# CAN.net
KiCad netlist of a schematic drawn in Altium Designer
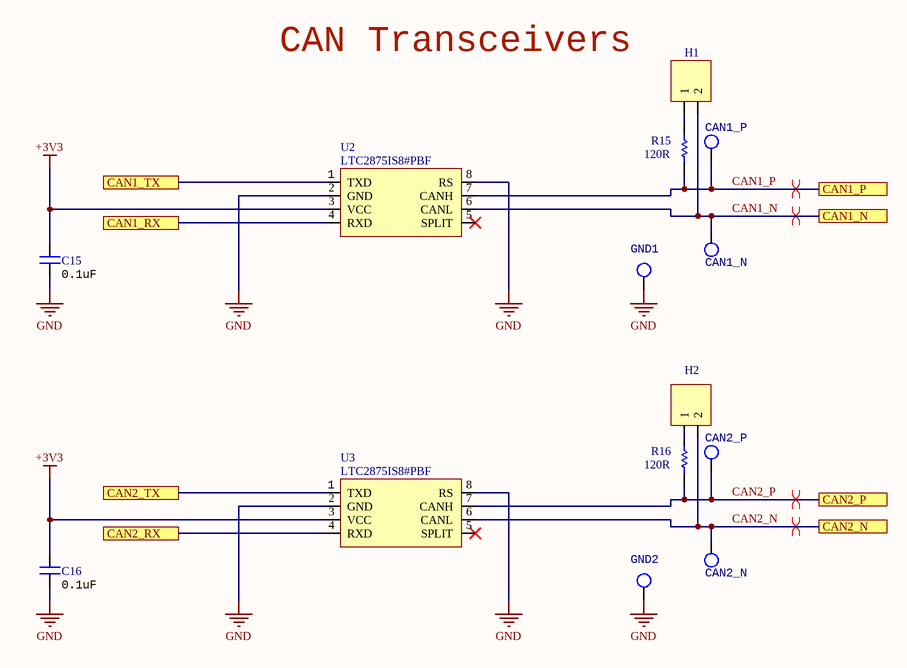
[diagram p0: CAN.SchDoc]

(export (version "E")
  (design (tool "Eeschema 10.0.6"))
  (components
    (comp (ref "C15")
      (value "0.1uF")
      (footprint "CAPC0603(1608)55_N")
      (description "CAP CER 0.1UF 16V X7R 0603")
      (fields (field (name "MPN") "CC0603KRX7R7BB104") (field (name "MANUFACTURER") "Yageo"))
      (libsource (lib "UWRT_Schematic_Library_2020") (part "CAP_0.1uF_16V_0603"))
    )
    (comp (ref "C16")
      (value "0.1uF")
      (footprint "CAPC0603(1608)55_N")
      (description "CAP CER 0.1UF 16V X7R 0603")
      (fields (field (name "MPN") "CC0603KRX7R7BB104") (field (name "MANUFACTURER") "Yageo"))
      (libsource (lib "UWRT_Schematic_Library_2020") (part "CAP_0.1uF_16V_0603"))
    )
    (comp (ref "CAN1_N")
      (value "TESTPOINT_LOOP")
      (footprint "TESTPOINT_LOOP")
      (description "Loop testpoint through-hole pad")
      (fields (field (name "MANUFACTURER") "Keystone Electronics"))
      (libsource (lib "UWRT_Schematic_Library_2020") (part "TESTPOINT_LOOP"))
    )
    (comp (ref "CAN1_P")
      (value "TESTPOINT_LOOP")
      (footprint "TESTPOINT_LOOP")
      (description "Loop testpoint through-hole pad")
      (fields (field (name "MANUFACTURER") "Keystone Electronics"))
      (libsource (lib "UWRT_Schematic_Library_2020") (part "TESTPOINT_LOOP"))
    )
    (comp (ref "CAN2_N")
      (value "TESTPOINT_LOOP")
      (footprint "TESTPOINT_LOOP")
      (description "Loop testpoint through-hole pad")
      (fields (field (name "MANUFACTURER") "Keystone Electronics"))
      (libsource (lib "UWRT_Schematic_Library_2020") (part "TESTPOINT_LOOP"))
    )
    (comp (ref "CAN2_P")
      (value "TESTPOINT_LOOP")
      (footprint "TESTPOINT_LOOP")
      (description "Loop testpoint through-hole pad")
      (fields (field (name "MANUFACTURER") "Keystone Electronics"))
      (libsource (lib "UWRT_Schematic_Library_2020") (part "TESTPOINT_LOOP"))
    )
    (comp (ref "GND1")
      (value "TESTPOINT_LOOP")
      (footprint "TESTPOINT_LOOP")
      (description "Loop testpoint through-hole pad")
      (fields (field (name "MANUFACTURER") "Keystone Electronics"))
      (libsource (lib "UWRT_Schematic_Library_2020") (part "TESTPOINT_LOOP"))
    )
    (comp (ref "GND2")
      (value "TESTPOINT_LOOP")
      (footprint "TESTPOINT_LOOP")
      (description "Loop testpoint through-hole pad")
      (fields (field (name "MANUFACTURER") "Keystone Electronics"))
      (libsource (lib "UWRT_Schematic_Library_2020") (part "TESTPOINT_LOOP"))
    )
    (comp (ref "H1")
      (value "JUMPER_2")
      (footprint "HDR1X2")
      (description "HEADER 2X1")
      (libsource (lib "UWRT_Schematic_Library_2020") (part "JUMPER_2"))
    )
    (comp (ref "H2")
      (value "JUMPER_2")
      (footprint "HDR1X2")
      (description "HEADER 2X1")
      (libsource (lib "UWRT_Schematic_Library_2020") (part "JUMPER_2"))
    )
    (comp (ref "R15")
      (value "120R")
      (footprint "RESC0603(1608)_N")
      (description "RES SMD 120 OHM 5% 1/10W 0603")
      (fields (field (name "MANUFACTURER") "Yageo") (field (name "MPN") "RC0603JR-07120RL"))
      (libsource (lib "UWRT_Schematic_Library_2020") (part "RES_120R_0603"))
    )
    (comp (ref "R16")
      (value "120R")
      (footprint "RESC0603(1608)_N")
      (description "RES SMD 120 OHM 5% 1/10W 0603")
      (fields (field (name "MANUFACTURER") "Yageo") (field (name "MPN") "RC0603JR-07120RL"))
      (libsource (lib "UWRT_Schematic_Library_2020") (part "RES_120R_0603"))
    )
    (comp (ref "U2")
      (value "IC TXRX CAN")
      (footprint "LT-S8_N")
      (description "IC TXRX CAN 4MBPS 8SO")
      (fields (field (name "MANUFACTURER") "Linear Technologies") (field (name "MPN") "LTC2875IS8#PBF"))
      (libsource (lib "UWRT_Schematic_Library_2020") (part "LTC2875"))
    )
    (comp (ref "U3")
      (value "IC TXRX CAN")
      (footprint "LT-S8_N")
      (description "IC TXRX CAN 4MBPS 8SO")
      (fields (field (name "MANUFACTURER") "Linear Technologies") (field (name "MPN") "LTC2875IS8#PBF"))
      (libsource (lib "UWRT_Schematic_Library_2020") (part "LTC2875"))
    )
  )
  (nets
    (net (code "1") (name "+3V3") (class "Default")
      (node (ref "C15") (pin "2") (pinfunction "2_2") (pintype "passive"))
      (node (ref "C16") (pin "2") (pinfunction "2_2") (pintype "passive"))
      (node (ref "U2") (pin "3") (pinfunction "VCC_3") (pintype "passive"))
      (node (ref "U3") (pin "3") (pinfunction "VCC_3") (pintype "passive"))
    )
    (net (code "2") (name "/CAN1_N") (class "Default")
      (node (ref "CAN1_N") (pin "1") (pintype "passive"))
      (node (ref "H1") (pin "2") (pinfunction "2_2") (pintype "passive"))
      (node (ref "U2") (pin "6") (pinfunction "CANL_6") (pintype "passive"))
    )
    (net (code "3") (name "/CAN1_P") (class "Default")
      (node (ref "CAN1_P") (pin "1") (pintype "passive"))
      (node (ref "R15") (pin "1") (pinfunction "1_1") (pintype "passive"))
      (node (ref "U2") (pin "7") (pinfunction "CANH_7") (pintype "passive"))
    )
    (net (code "4") (name "/CAN1_RX") (class "Default")
      (node (ref "U2") (pin "4") (pinfunction "RXD_4") (pintype "passive"))
    )
    (net (code "5") (name "/CAN1_TX") (class "Default")
      (node (ref "U2") (pin "1") (pinfunction "TXD_1") (pintype "passive"))
    )
    (net (code "6") (name "/CAN2_N") (class "Default")
      (node (ref "CAN2_N") (pin "1") (pintype "passive"))
      (node (ref "H2") (pin "2") (pinfunction "2_2") (pintype "passive"))
      (node (ref "U3") (pin "6") (pinfunction "CANL_6") (pintype "passive"))
    )
    (net (code "7") (name "/CAN2_P") (class "Default")
      (node (ref "CAN2_P") (pin "1") (pintype "passive"))
      (node (ref "R16") (pin "1") (pinfunction "1_1") (pintype "passive"))
      (node (ref "U3") (pin "7") (pinfunction "CANH_7") (pintype "passive"))
    )
    (net (code "8") (name "/CAN2_RX") (class "Default")
      (node (ref "U3") (pin "4") (pinfunction "RXD_4") (pintype "passive"))
    )
    (net (code "9") (name "/CAN2_TX") (class "Default")
      (node (ref "U3") (pin "1") (pinfunction "TXD_1") (pintype "passive"))
    )
    (net (code "10") (name "GND") (class "Default")
      (node (ref "C15") (pin "1") (pinfunction "1_1") (pintype "passive"))
      (node (ref "C16") (pin "1") (pinfunction "1_1") (pintype "passive"))
      (node (ref "GND1") (pin "1") (pintype "passive"))
      (node (ref "GND2") (pin "1") (pintype "passive"))
      (node (ref "U2") (pin "2") (pinfunction "GND_2") (pintype "passive"))
      (node (ref "U2") (pin "8") (pinfunction "RS_8") (pintype "passive"))
      (node (ref "U3") (pin "2") (pinfunction "GND_2") (pintype "passive"))
      (node (ref "U3") (pin "8") (pinfunction "RS_8") (pintype "passive"))
    )
    (net (code "11") (name "Net-(H1-Pad1)") (class "Default")
      (node (ref "H1") (pin "1") (pinfunction "1_1") (pintype "passive"))
      (node (ref "R15") (pin "2") (pinfunction "2_2") (pintype "passive"))
    )
    (net (code "12") (name "Net-(H2-Pad1)") (class "Default")
      (node (ref "H2") (pin "1") (pinfunction "1_1") (pintype "passive"))
      (node (ref "R16") (pin "2") (pinfunction "2_2") (pintype "passive"))
    )
    (net (code "13") (name "unconnected-(U2-SPLIT-Pad5)") (class "Default")
      (node (ref "U2") (pin "5") (pinfunction "SPLIT_5") (pintype "passive+no_connect"))
    )
    (net (code "14") (name "unconnected-(U3-SPLIT-Pad5)") (class "Default")
      (node (ref "U3") (pin "5") (pinfunction "SPLIT_5") (pintype "passive+no_connect"))
    )
  )
)
